# Top.net
KiCad netlist of a schematic drawn in Altium Designer
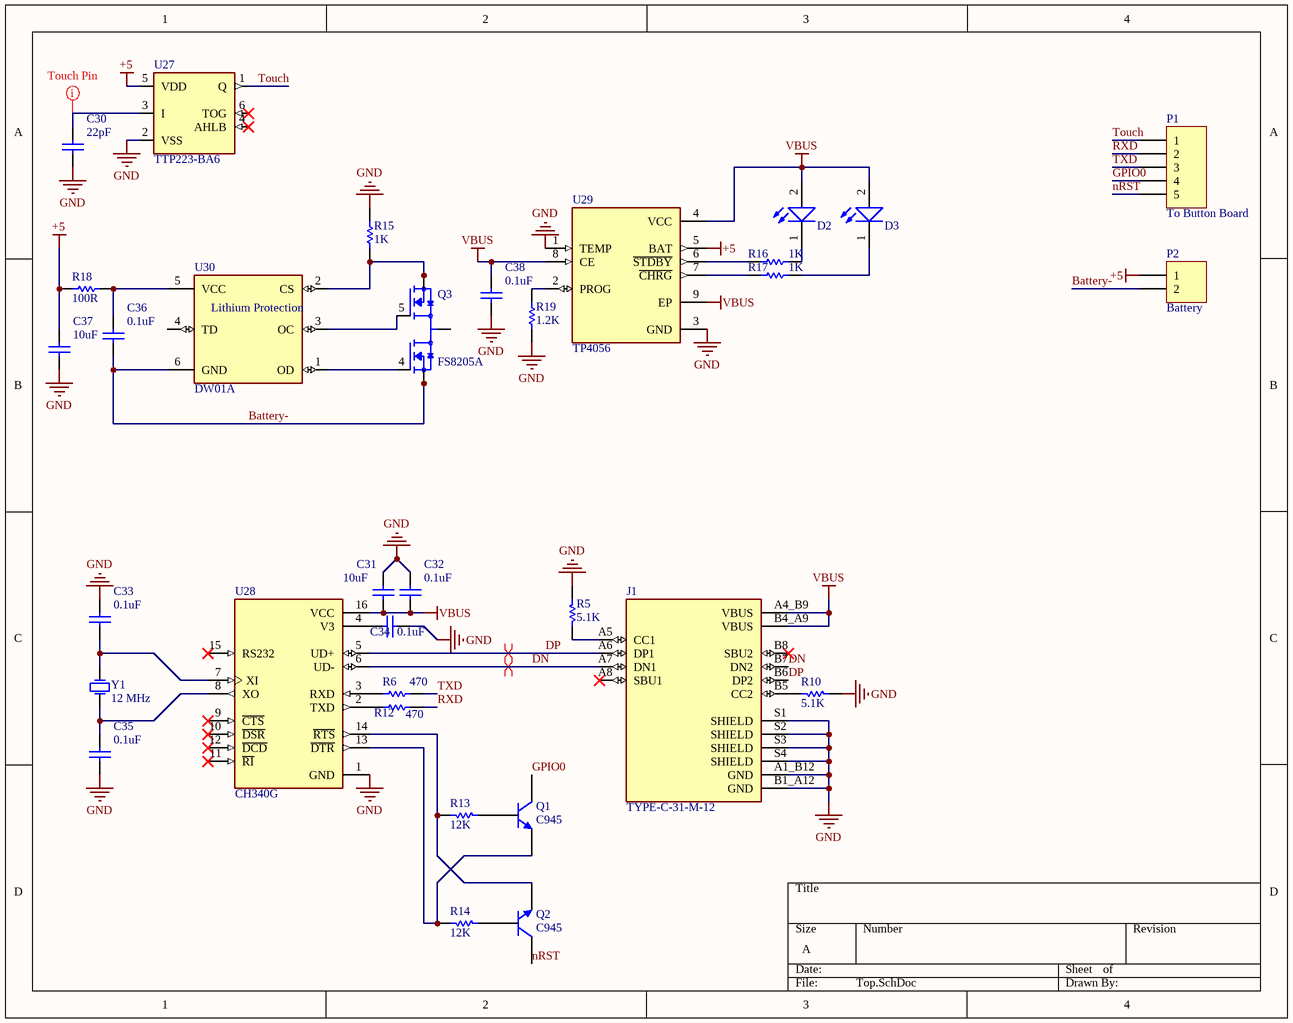
[diagram p0: Top.SchDoc]

(export (version "E")
  (design (tool "Eeschema 10.0.6"))
  (components
    (comp (ref "C30")
      (value "22pF")
      (footprint "CAPC3413X12N")
      (description "CAP 0805")
      (fields (field (name "DESIGNER") "Abbas Basereh"))
      (libsource (lib "Altium") (part "CAP SMD 0805"))
    )
    (comp (ref "C31")
      (value "10uF")
      (footprint "CAPC3413X12N")
      (description "CAP 0805")
      (fields (field (name "DESIGNER") "Abbas Basereh"))
      (libsource (lib "Altium") (part "CAP SMD 0805"))
    )
    (comp (ref "C32")
      (value "0.1uF")
      (footprint "CAPC3413X12N")
      (description "CAP 0805")
      (fields (field (name "DESIGNER") "Abbas Basereh"))
      (libsource (lib "Altium") (part "CAP SMD 0805"))
    )
    (comp (ref "C33")
      (value "0.1uF")
      (footprint "CAPC3413X12N")
      (description "CAP 0805")
      (fields (field (name "DESIGNER") "Abbas Basereh"))
      (libsource (lib "Altium") (part "CAP SMD 0805"))
    )
    (comp (ref "C34")
      (value "0.1uF")
      (footprint "CAPC3413X12N")
      (description "CAP 0805")
      (fields (field (name "DESIGNER") "Abbas Basereh"))
      (libsource (lib "Altium") (part "CAP SMD 0805"))
    )
    (comp (ref "C35")
      (value "0.1uF")
      (footprint "CAPC3413X12N")
      (description "CAP 0805")
      (fields (field (name "DESIGNER") "Abbas Basereh"))
      (libsource (lib "Altium") (part "CAP SMD 0805"))
    )
    (comp (ref "C36")
      (value "0.1uF")
      (footprint "CAPC3413X12N")
      (description "CAP 0805")
      (fields (field (name "DESIGNER") "Abbas Basereh"))
      (libsource (lib "Altium") (part "CAP SMD 0805"))
    )
    (comp (ref "C37")
      (value "10uF")
      (footprint "CAPC3413X12N")
      (description "CAP 0805")
      (fields (field (name "DESIGNER") "Abbas Basereh"))
      (libsource (lib "Altium") (part "CAP SMD 0805"))
    )
    (comp (ref "C38")
      (value "0.1uF")
      (footprint "CAPC3413X12N")
      (description "CAP 0805")
      (fields (field (name "DESIGNER") "Abbas Basereh"))
      (libsource (lib "Altium") (part "CAP SMD 0805"))
    )
    (comp (ref "D2")
      (value "LED SMD PACKAGE")
      (footprint "LED_SMD_0805")
      (description "SMD Mono-color Chip LED Waterclear")
      (fields (field (name "PART NUMBER") "150080BS75000") (field (name "PUBLISHER") "Ali Hafizi"))
      (libsource (lib "Altium") (part "LED SMD PACKAGE"))
    )
    (comp (ref "D3")
      (value "LED SMD PACKAGE")
      (footprint "LED_SMD_0805")
      (description "SMD Mono-color Chip LED Waterclear")
      (fields (field (name "PART NUMBER") "150080BS75000") (field (name "PUBLISHER") "Ali Hafizi"))
      (libsource (lib "Altium") (part "LED SMD PACKAGE"))
    )
    (comp (ref "J1")
      (value "TYPE-C-31-M-12")
      (footprint "HRO_TYPE-C-31-M-12")
      (description "USB Connectors 24 Receptacle 1 8.94*7.3mm RoHS")
      (fields (field (name "MF") "HRO Electronics Co., Ltd."))
      (libsource (lib "TYPE-C-31-M-12") (part "TYPE-C-31-M-12"))
    )
    (comp (ref "P1")
      (value "To Button Board")
      (footprint "HDR1X5")
      (description "Header, 5-Pin")
      (fields (field (name "PUBLISHER") "Altium Limited"))
      (libsource (lib "Altium") (part "Header 5"))
    )
    (comp (ref "P2")
      (value "Battery")
      (footprint "HDR1X2")
      (description "Header, 2-Pin")
      (fields (field (name "PUBLISHER") "Altium Limited"))
      (libsource (lib "Altium") (part "Header 2"))
    )
    (comp (ref "Q1")
      (value "C945")
      (footprint "SOT23_N")
      (description "NPN Silicon Epitaxial Planar Transistor")
      (fields (field (name "PUBLISHER") "Abbas Basereh"))
      (libsource (lib "Altium") (part "C945"))
    )
    (comp (ref "Q2")
      (value "C945")
      (footprint "SOT23_N")
      (description "NPN Silicon Epitaxial Planar Transistor")
      (fields (field (name "PUBLISHER") "Abbas Basereh"))
      (libsource (lib "Altium") (part "C945"))
    )
    (comp (ref "Q3")
      (value "FS8205A")
      (footprint "SOP65P640X120-8N")
      (fields (field (name "MF") "Fortune Semiconductor"))
      (libsource (lib "FS8205A") (part "FS8205A"))
    )
    (comp (ref "R5")
      (value "5.1K")
      (footprint "RES0805")
      (description "TOTAL SMD RESISTOR PACK")
      (fields (field (name "DESIGNER") "Abbas Basereh"))
      (libsource (lib "Altium") (part "RES SMD PACKAGE"))
    )
    (comp (ref "R6")
      (value "470")
      (footprint "RES0805")
      (description "TOTAL SMD RESISTOR PACK")
      (fields (field (name "DESIGNER") "Abbas Basereh"))
      (libsource (lib "Altium") (part "RES SMD PACKAGE"))
    )
    (comp (ref "R10")
      (value "5.1K")
      (footprint "RES0805")
      (description "TOTAL SMD RESISTOR PACK")
      (fields (field (name "DESIGNER") "Abbas Basereh"))
      (libsource (lib "Altium") (part "RES SMD PACKAGE"))
    )
    (comp (ref "R12")
      (value "470")
      (footprint "RES0805")
      (description "TOTAL SMD RESISTOR PACK")
      (fields (field (name "DESIGNER") "Abbas Basereh"))
      (libsource (lib "Altium") (part "RES SMD PACKAGE"))
    )
    (comp (ref "R13")
      (value "12K")
      (footprint "RES0805")
      (description "TOTAL SMD RESISTOR PACK")
      (fields (field (name "DESIGNER") "Abbas Basereh"))
      (libsource (lib "Altium") (part "RES SMD PACKAGE"))
    )
    (comp (ref "R14")
      (value "12K")
      (footprint "RES0805")
      (description "TOTAL SMD RESISTOR PACK")
      (fields (field (name "DESIGNER") "Abbas Basereh"))
      (libsource (lib "Altium") (part "RES SMD PACKAGE"))
    )
    (comp (ref "R15")
      (value "1K")
      (footprint "RESC3413X04N")
      (description "RES 0805")
      (fields (field (name "DESIGNER") "Abbas Basereh"))
      (libsource (lib "Altium") (part "RES 0805 0.125W"))
    )
    (comp (ref "R16")
      (value "1K")
      (footprint "RESC3413X04N")
      (description "RES 0805")
      (fields (field (name "DESIGNER") "Abbas Basereh"))
      (libsource (lib "Altium") (part "RES 0805 0.125W"))
    )
    (comp (ref "R17")
      (value "1K")
      (footprint "RESC3413X04N")
      (description "RES 0805")
      (fields (field (name "DESIGNER") "Abbas Basereh"))
      (libsource (lib "Altium") (part "RES 0805 0.125W"))
    )
    (comp (ref "R18")
      (value "100R")
      (footprint "RESC3413X04N")
      (description "RES 0805")
      (fields (field (name "DESIGNER") "Abbas Basereh"))
      (libsource (lib "Altium") (part "RES 0805 0.125W"))
    )
    (comp (ref "R19")
      (value "1.2K")
      (footprint "RESC3413X04N")
      (description "RES 0805")
      (fields (field (name "DESIGNER") "Abbas Basereh"))
      (libsource (lib "Altium") (part "RES 0805 0.125W"))
    )
    (comp (ref "U27")
      (value "TTP223-BA6")
      (footprint "SOT23-6")
      (fields (field (name "MF") "tontek"))
      (libsource (lib "TTP223-BA6") (part "TTP223-BA6"))
    )
    (comp (ref "U28")
      (value "CH340G")
      (footprint "SOIC127P600X180-16N")
      (description "USB Interface Integrated Circuit")
      (fields (field (name "MP") "Ch340G") (field (name "MF") "WCH"))
      (libsource (lib "CH340G") (part "CH340G"))
    )
    (comp (ref "U29")
      (value "TP4056")
      (footprint "SOP127P600X175-9N")
      (description "Complete single cell Li-Ion battery with a constant current / constant voltage linear charger")
      (fields (field (name "MF") "NanJing Top Power ASIC Corp."))
      (libsource (lib "TP4056") (part "TP4056"))
    )
    (comp (ref "U30")
      (value "DW01A")
      (footprint "SOT23-6")
      (description "One Cell Lithium-ion/Polymer Battery Protection IC")
      (fields (field (name "MF") "Fortune Semiconductor"))
      (libsource (lib "DW01A") (part "DW01A"))
    )
    (comp (ref "Y1")
      (value "12 MHz")
      (footprint "Crystal SMD")
      (description "XTAL Crystal")
      (fields (field (name "DESIGNER") "ABBAS BASEREH"))
      (libsource (lib "Altium") (part "XTAL"))
    )
  )
  (nets
    (net (code "1") (name "+5") (class "Default")
      (node (ref "C37") (pin "1") (pinfunction "1_1") (pintype "passive"))
      (node (ref "P2") (pin "1") (pinfunction "1_1") (pintype "passive"))
      (node (ref "R18") (pin "1") (pinfunction "1_1") (pintype "passive"))
      (node (ref "U27") (pin "5") (pinfunction "VDD_5") (pintype "power_in"))
      (node (ref "U29") (pin "5") (pinfunction "BAT_5") (pintype "output"))
    )
    (net (code "2") (name "/Battery-") (class "Default")
      (node (ref "C36") (pin "2") (pinfunction "2_2") (pintype "passive"))
      (node (ref "P2") (pin "2") (pinfunction "2_2") (pintype "passive"))
      (node (ref "Q3") (pin "2") (pinfunction "S1_2") (pintype "passive"))
      (node (ref "Q3") (pin "3") (pinfunction "S1_3") (pintype "passive"))
      (node (ref "U30") (pin "6") (pinfunction "GND_6") (pintype "power_in"))
    )
    (net (code "3") (name "/DN") (class "Default")
      (node (ref "J1") (pin "A7") (pinfunction "DN1_A7") (pintype "bidirectional"))
      (node (ref "J1") (pin "B7") (pinfunction "DN2_B7") (pintype "bidirectional"))
      (node (ref "U28") (pin "6") (pinfunction "UD-_6") (pintype "bidirectional"))
    )
    (net (code "4") (name "/DP") (class "Default")
      (node (ref "J1") (pin "A6") (pinfunction "DP1_A6") (pintype "bidirectional"))
      (node (ref "J1") (pin "B6") (pinfunction "DP2_B6") (pintype "bidirectional"))
      (node (ref "U28") (pin "5") (pinfunction "UD+_5") (pintype "bidirectional"))
    )
    (net (code "5") (name "/GPIO0") (class "Default")
      (node (ref "P1") (pin "4") (pinfunction "4_4") (pintype "passive"))
      (node (ref "Q1") (pin "3") (pinfunction "C_3") (pintype "passive"))
    )
    (net (code "6") (name "/RXD") (class "Default")
      (node (ref "P1") (pin "2") (pinfunction "2_2") (pintype "passive"))
      (node (ref "R12") (pin "2") (pinfunction "2_2") (pintype "passive"))
    )
    (net (code "7") (name "/TXD") (class "Default")
      (node (ref "P1") (pin "3") (pinfunction "3_3") (pintype "passive"))
      (node (ref "R6") (pin "2") (pinfunction "2_2") (pintype "passive"))
    )
    (net (code "8") (name "/Touch") (class "Default")
      (node (ref "P1") (pin "1") (pinfunction "1_1") (pintype "passive"))
      (node (ref "U27") (pin "1") (pinfunction "Q_1") (pintype "output"))
    )
    (net (code "9") (name "/nRST") (class "Default")
      (node (ref "P1") (pin "5") (pinfunction "5_5") (pintype "passive"))
      (node (ref "Q2") (pin "3") (pinfunction "C_3") (pintype "passive"))
    )
    (net (code "10") (name "GND") (class "Default")
      (node (ref "C30") (pin "2") (pinfunction "2_2") (pintype "passive"))
      (node (ref "C31") (pin "1") (pinfunction "1_1") (pintype "passive"))
      (node (ref "C32") (pin "1") (pinfunction "1_1") (pintype "passive"))
      (node (ref "C33") (pin "1") (pinfunction "1_1") (pintype "passive"))
      (node (ref "C34") (pin "1") (pinfunction "1_1") (pintype "passive"))
      (node (ref "C35") (pin "2") (pinfunction "2_2") (pintype "passive"))
      (node (ref "C37") (pin "2") (pinfunction "2_2") (pintype "passive"))
      (node (ref "C38") (pin "2") (pinfunction "2_2") (pintype "passive"))
      (node (ref "J1") (pin "A1_B12") (pinfunction "GND_A1_B12") (pintype "power_in"))
      (node (ref "J1") (pin "B1_A12") (pinfunction "GND_B1_A12") (pintype "power_in"))
      (node (ref "J1") (pin "S1") (pinfunction "SHIELD_S1") (pintype "passive"))
      (node (ref "J1") (pin "S2") (pinfunction "SHIELD_S2") (pintype "passive"))
      (node (ref "J1") (pin "S3") (pinfunction "SHIELD_S3") (pintype "passive"))
      (node (ref "J1") (pin "S4") (pinfunction "SHIELD_S4") (pintype "passive"))
      (node (ref "R10") (pin "1") (pinfunction "1_1") (pintype "passive"))
      (node (ref "R15") (pin "1") (pinfunction "1_1") (pintype "passive"))
      (node (ref "R19") (pin "1") (pinfunction "1_1") (pintype "passive"))
      (node (ref "R5") (pin "1") (pinfunction "1_1") (pintype "passive"))
      (node (ref "U27") (pin "2") (pinfunction "VSS_2") (pintype "power_in"))
      (node (ref "U28") (pin "1") (pinfunction "GND_1") (pintype "power_in"))
      (node (ref "U29") (pin "1") (pinfunction "TEMP_1") (pintype "input"))
      (node (ref "U29") (pin "3") (pinfunction "GND_3") (pintype "power_in"))
    )
    (net (code "11") (name "Net-(D2-K)") (class "Default")
      (node (ref "D2") (pin "1") (pinfunction "K_1") (pintype "passive"))
      (node (ref "R16") (pin "2") (pinfunction "2_2") (pintype "passive"))
    )
    (net (code "12") (name "Net-(D3-K)") (class "Default")
      (node (ref "D3") (pin "1") (pinfunction "K_1") (pintype "passive"))
      (node (ref "R17") (pin "2") (pinfunction "2_2") (pintype "passive"))
    )
    (net (code "13") (name "Net-(J1-CC1)") (class "Default")
      (node (ref "J1") (pin "A5") (pinfunction "CC1_A5") (pintype "bidirectional"))
      (node (ref "R5") (pin "2") (pinfunction "2_2") (pintype "passive"))
    )
    (net (code "14") (name "Net-(J1-CC2)") (class "Default")
      (node (ref "J1") (pin "B5") (pinfunction "CC2_B5") (pintype "bidirectional"))
      (node (ref "R10") (pin "2") (pinfunction "2_2") (pintype "passive"))
    )
    (net (code "15") (name "Net-(Q1-B)") (class "Default")
      (node (ref "Q1") (pin "1") (pinfunction "B_1") (pintype "passive"))
      (node (ref "R13") (pin "2") (pinfunction "2_2") (pintype "passive"))
    )
    (net (code "16") (name "Net-(Q1-E)") (class "Default")
      (node (ref "Q1") (pin "2") (pinfunction "E_2") (pintype "passive"))
      (node (ref "R14") (pin "1") (pinfunction "1_1") (pintype "passive"))
      (node (ref "U28") (pin "13") (pinfunction "~{DTR}_13") (pintype "output"))
    )
    (net (code "17") (name "Net-(Q2-B)") (class "Default")
      (node (ref "Q2") (pin "1") (pinfunction "B_1") (pintype "passive"))
      (node (ref "R14") (pin "2") (pinfunction "2_2") (pintype "passive"))
    )
    (net (code "18") (name "Net-(Q2-E)") (class "Default")
      (node (ref "Q2") (pin "2") (pinfunction "E_2") (pintype "passive"))
      (node (ref "R13") (pin "1") (pinfunction "1_1") (pintype "passive"))
      (node (ref "U28") (pin "14") (pinfunction "~{RTS}_14") (pintype "output"))
    )
    (net (code "19") (name "Net-(Q3-D12-Pad1)") (class "Default")
      (node (ref "Q3") (pin "1") (pinfunction "D12_1") (pintype "passive"))
      (node (ref "Q3") (pin "8") (pinfunction "D12_8") (pintype "passive"))
    )
    (net (code "20") (name "Net-(Q3-G1)") (class "Default")
      (node (ref "Q3") (pin "4") (pinfunction "G1_4") (pintype "passive"))
      (node (ref "U30") (pin "1") (pinfunction "OD_1") (pintype "bidirectional"))
    )
    (net (code "21") (name "Net-(Q3-G2)") (class "Default")
      (node (ref "Q3") (pin "5") (pinfunction "G2_5") (pintype "passive"))
      (node (ref "U30") (pin "3") (pinfunction "OC_3") (pintype "bidirectional"))
    )
    (net (code "22") (name "Net-(U27-I)") (class "Default")
      (node (ref "C30") (pin "1") (pinfunction "1_1") (pintype "passive"))
      (node (ref "U27") (pin "3") (pinfunction "I_3") (pintype "bidirectional"))
    )
    (net (code "23") (name "Net-(U28-RXD)") (class "Default")
      (node (ref "R6") (pin "1") (pinfunction "1_1") (pintype "passive"))
      (node (ref "U28") (pin "3") (pinfunction "RXD_3") (pintype "input"))
    )
    (net (code "24") (name "Net-(U28-TXD)") (class "Default")
      (node (ref "R12") (pin "1") (pinfunction "1_1") (pintype "passive"))
      (node (ref "U28") (pin "2") (pinfunction "TXD_2") (pintype "output"))
    )
    (net (code "25") (name "Net-(U28-V3)") (class "Default")
      (node (ref "C34") (pin "2") (pinfunction "2_2") (pintype "passive"))
      (node (ref "U28") (pin "4") (pinfunction "V3_4") (pintype "power_in"))
    )
    (net (code "26") (name "Net-(U28-XI)") (class "Default")
      (node (ref "C33") (pin "2") (pinfunction "2_2") (pintype "passive"))
      (node (ref "U28") (pin "7") (pinfunction "XI_7") (pintype "input"))
      (node (ref "Y1") (pin "2") (pinfunction "OSC2_2") (pintype "passive"))
    )
    (net (code "27") (name "Net-(U28-XO)") (class "Default")
      (node (ref "C35") (pin "1") (pinfunction "1_1") (pintype "passive"))
      (node (ref "U28") (pin "8") (pinfunction "XO_8") (pintype "output"))
      (node (ref "Y1") (pin "1") (pinfunction "OSC1_1") (pintype "passive"))
    )
    (net (code "28") (name "Net-(U29-PROG)") (class "Default")
      (node (ref "R19") (pin "2") (pinfunction "2_2") (pintype "passive"))
      (node (ref "U29") (pin "2") (pinfunction "PROG_2") (pintype "bidirectional"))
    )
    (net (code "29") (name "Net-(U29-~{CHRG})") (class "Default")
      (node (ref "R17") (pin "1") (pinfunction "1_1") (pintype "passive"))
      (node (ref "U29") (pin "7") (pinfunction "~{CHRG}_7") (pintype "output"))
    )
    (net (code "30") (name "Net-(U29-~{STDBY})") (class "Default")
      (node (ref "R16") (pin "1") (pinfunction "1_1") (pintype "passive"))
      (node (ref "U29") (pin "6") (pinfunction "~{STDBY}_6") (pintype "output"))
    )
    (net (code "31") (name "Net-(U30-CS)") (class "Default")
      (node (ref "Q3") (pin "6") (pinfunction "S2_6") (pintype "passive"))
      (node (ref "Q3") (pin "7") (pinfunction "S2_7") (pintype "passive"))
      (node (ref "R15") (pin "2") (pinfunction "2_2") (pintype "passive"))
      (node (ref "U30") (pin "2") (pinfunction "CS_2") (pintype "bidirectional"))
    )
    (net (code "32") (name "Net-(U30-VCC)") (class "Default")
      (node (ref "C36") (pin "1") (pinfunction "1_1") (pintype "passive"))
      (node (ref "R18") (pin "2") (pinfunction "2_2") (pintype "passive"))
      (node (ref "U30") (pin "5") (pinfunction "VCC_5") (pintype "power_in"))
    )
    (net (code "33") (name "VBUS") (class "Default")
      (node (ref "C31") (pin "2") (pinfunction "2_2") (pintype "passive"))
      (node (ref "C32") (pin "2") (pinfunction "2_2") (pintype "passive"))
      (node (ref "C38") (pin "1") (pinfunction "1_1") (pintype "passive"))
      (node (ref "D2") (pin "2") (pinfunction "A_2") (pintype "passive"))
      (node (ref "D3") (pin "2") (pinfunction "A_2") (pintype "passive"))
      (node (ref "J1") (pin "A4_B9") (pinfunction "VBUS_A4_B9") (pintype "power_in"))
      (node (ref "J1") (pin "B4_A9") (pinfunction "VBUS_B4_A9") (pintype "power_in"))
      (node (ref "U28") (pin "16") (pinfunction "VCC_16") (pintype "power_in"))
      (node (ref "U29") (pin "4") (pinfunction "VCC_4") (pintype "power_in"))
      (node (ref "U29") (pin "8") (pinfunction "CE_8") (pintype "input"))
      (node (ref "U29") (pin "9") (pinfunction "EP_9") (pintype "passive"))
    )
    (net (code "34") (name "unconnected-(J1-SBU1-PadA8)") (class "Default")
      (node (ref "J1") (pin "A8") (pinfunction "SBU1_A8") (pintype "bidirectional+no_connect"))
    )
    (net (code "35") (name "unconnected-(J1-SBU2-PadB8)") (class "Default")
      (node (ref "J1") (pin "B8") (pinfunction "SBU2_B8") (pintype "bidirectional+no_connect"))
    )
    (net (code "36") (name "unconnected-(U27-AHLB-Pad4)") (class "Default")
      (node (ref "U27") (pin "4") (pinfunction "AHLB_4") (pintype "input+no_connect"))
    )
    (net (code "37") (name "unconnected-(U27-TOG-Pad6)") (class "Default")
      (node (ref "U27") (pin "6") (pinfunction "TOG_6") (pintype "input+no_connect"))
    )
    (net (code "38") (name "unconnected-(U28-RS232-Pad15)") (class "Default")
      (node (ref "U28") (pin "15") (pinfunction "RS232_15") (pintype "input+no_connect"))
    )
    (net (code "39") (name "unconnected-(U28-~{CTS}-Pad9)") (class "Default")
      (node (ref "U28") (pin "9") (pinfunction "~{CTS}_9") (pintype "input+no_connect"))
    )
    (net (code "40") (name "unconnected-(U28-~{DCD}-Pad12)") (class "Default")
      (node (ref "U28") (pin "12") (pinfunction "~{DCD}_12") (pintype "input+no_connect"))
    )
    (net (code "41") (name "unconnected-(U28-~{DSR}-Pad10)") (class "Default")
      (node (ref "U28") (pin "10") (pinfunction "~{DSR}_10") (pintype "input+no_connect"))
    )
    (net (code "42") (name "unconnected-(U28-~{RI}-Pad11)") (class "Default")
      (node (ref "U28") (pin "11") (pinfunction "~{RI}_11") (pintype "input+no_connect"))
    )
    (net (code "43") (name "unconnected-(U30-TD-Pad4)") (class "Default")
      (node (ref "U30") (pin "4") (pinfunction "TD_4") (pintype "bidirectional"))
    )
  )
)
